# debug.net
KiCad netlist of a schematic drawn in Altium Designer
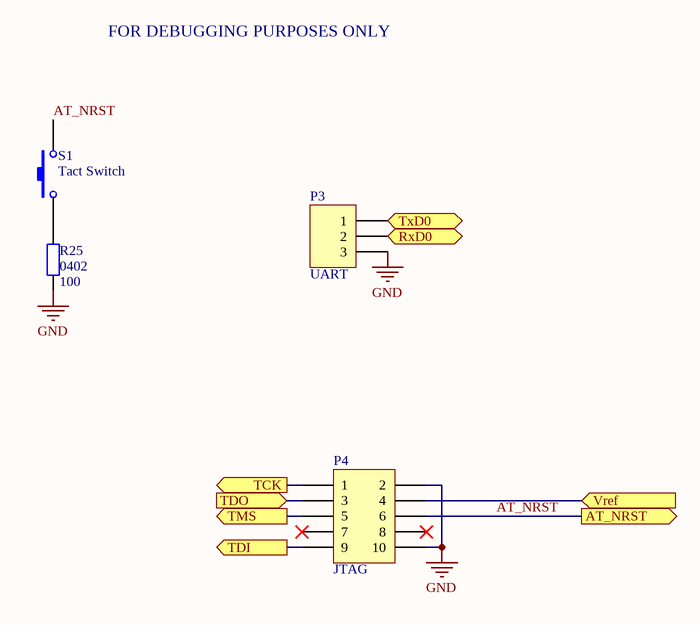
[diagram p0: debug.SchDoc]

(export (version "E")
  (design (tool "Eeschema 10.0.6"))
  (components
    (comp (ref "P3")
      (value "UART")
      (footprint "HDR1X3")
      (description "Header, 3-Pin")
      (fields (field (name "PUBLISHER") "Altium Limited"))
      (libsource (lib "Miscellaneous Connectors") (part "Header 3"))
    )
    (comp (ref "P4")
      (value "JTAG")
      (footprint "HDR2X5")
      (description "Header, 5-Pin, Dual row")
      (fields (field (name "PUBLISHER") "Altium Limited"))
      (libsource (lib "Miscellaneous Connectors") (part "Header 5X2"))
    )
    (comp (ref "R25")
      (value "0402")
      (footprint "SMD_Capacitor_0402")
      (description "Resistor")
      (fields (field (name "ALTIUM_VALUE") "100") (field (name "PUBLISHER") "Altium Limited"))
      (libsource (lib "Miscellaneous Devices") (part "Res2"))
    )
    (comp (ref "S1")
      (value "Tact Switch")
      (footprint "Tact Switch 3x6")
      (libsource (lib "microswitch") (part "TactSwitch"))
    )
  )
  (nets
    (net (code "1") (name "/AT_NRST") (class "Default")
      (node (ref "P4") (pin "6") (pinfunction "6_6") (pintype "passive"))
      (node (ref "S1") (pin "2") (pinfunction "2_2") (pintype "passive"))
    )
    (net (code "2") (name "/RxD0") (class "Default")
      (node (ref "P3") (pin "2") (pinfunction "2_2") (pintype "passive"))
    )
    (net (code "3") (name "/TCK") (class "Default")
      (node (ref "P4") (pin "1") (pinfunction "1_1") (pintype "passive"))
    )
    (net (code "4") (name "/TDI") (class "Default")
      (node (ref "P4") (pin "9") (pinfunction "9_9") (pintype "passive"))
    )
    (net (code "5") (name "/TDO") (class "Default")
      (node (ref "P4") (pin "3") (pinfunction "3_3") (pintype "passive"))
    )
    (net (code "6") (name "/TMS") (class "Default")
      (node (ref "P4") (pin "5") (pinfunction "5_5") (pintype "passive"))
    )
    (net (code "7") (name "/TxD0") (class "Default")
      (node (ref "P3") (pin "1") (pinfunction "1_1") (pintype "passive"))
    )
    (net (code "8") (name "/Vref") (class "Default")
      (node (ref "P4") (pin "4") (pinfunction "4_4") (pintype "passive"))
    )
    (net (code "9") (name "GND") (class "Default")
      (node (ref "P3") (pin "3") (pinfunction "3_3") (pintype "passive"))
      (node (ref "P4") (pin "10") (pinfunction "10_10") (pintype "passive"))
      (node (ref "P4") (pin "2") (pinfunction "2_2") (pintype "passive"))
      (node (ref "R25") (pin "2") (pinfunction "2_2") (pintype "passive"))
    )
    (net (code "10") (name "Net-(R25-Pad1)") (class "Default")
      (node (ref "R25") (pin "1") (pinfunction "1_1") (pintype "passive"))
      (node (ref "S1") (pin "1") (pinfunction "1_1") (pintype "passive"))
    )
    (net (code "11") (name "unconnected-(P4-Pad7)") (class "Default")
      (node (ref "P4") (pin "7") (pinfunction "7_7") (pintype "passive+no_connect"))
    )
    (net (code "12") (name "unconnected-(P4-Pad8)") (class "Default")
      (node (ref "P4") (pin "8") (pinfunction "8_8") (pintype "passive+no_connect"))
    )
  )
)
